# MosFetsDrive_2.net
KiCad netlist of a schematic drawn in Altium Designer
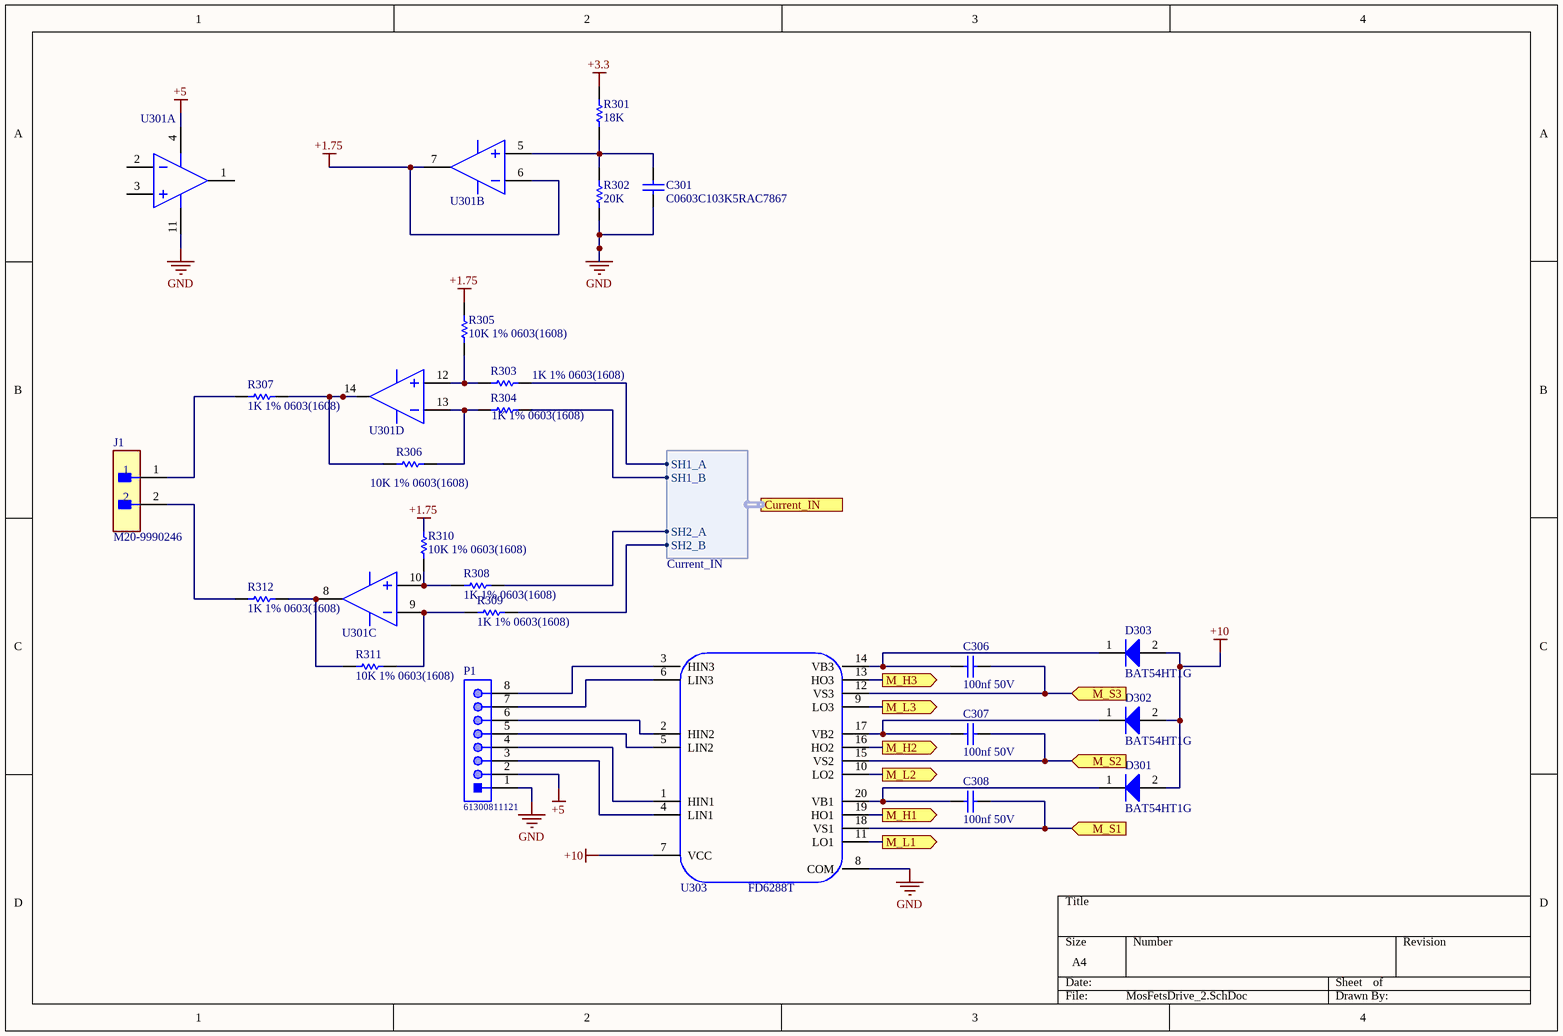
[diagram p0: MosFetsDrive_2.SchDoc]

(export (version "E")
  (design (tool "Eeschema 10.0.6"))
  (components
    (comp (ref "C301")
      (value "C0603C103K5RAC7867")
      (footprint "CAPC1608X87X35ML15T15")
      (fields (field (name "MANUFACTURER") "Kemet"))
      (libsource (lib "Altium Content Vault") (part "CAP"))
    )
    (comp (ref "C306")
      (value "100nf 50V")
      (footprint "CAPC1608X90X35LL15T15")
      (fields
        (field (name "MANUFACTURER") "AVX Interconnect / Elco")
        (field (name "PART NUMBER") "06035C102KAT2A")
      )
      (libsource (lib "Altium Content Vault") (part "CAP"))
    )
    (comp (ref "C307")
      (value "100nf 50V")
      (footprint "CAPC1608X90X35LL15T15")
      (fields
        (field (name "MANUFACTURER") "AVX Interconnect / Elco")
        (field (name "PART NUMBER") "06035C102KAT2A")
      )
      (libsource (lib "Altium Content Vault") (part "CAP"))
    )
    (comp (ref "C308")
      (value "100nf 50V")
      (footprint "CAPC1608X90X35LL15T15")
      (fields
        (field (name "MANUFACTURER") "AVX Interconnect / Elco")
        (field (name "PART NUMBER") "06035C102KAT2A")
      )
      (libsource (lib "Altium Content Vault") (part "CAP"))
    )
    (comp (ref "D301")
      (value "BAT54HT1G")
      (footprint "ONSC-SOD-323-2-477-02_V")
      (description "Schottky Barrier Diode, 2-Pin SOD-323, Pb-Free, Tape and Reel")
      (fields (field (name "MANUFACTURER") "On Semiconductor"))
      (libsource (lib "Altium Content Vault") (part "ONSC-D-K1A2-2"))
    )
    (comp (ref "D302")
      (value "BAT54HT1G")
      (footprint "ONSC-SOD-323-2-477-02_V")
      (description "Schottky Barrier Diode, 2-Pin SOD-323, Pb-Free, Tape and Reel")
      (fields (field (name "MANUFACTURER") "On Semiconductor"))
      (libsource (lib "Altium Content Vault") (part "ONSC-D-K1A2-2"))
    )
    (comp (ref "D303")
      (value "BAT54HT1G")
      (footprint "ONSC-SOD-323-2-477-02_V")
      (description "Schottky Barrier Diode, 2-Pin SOD-323, Pb-Free, Tape and Reel")
      (fields (field (name "MANUFACTURER") "On Semiconductor"))
      (libsource (lib "Altium Content Vault") (part "ONSC-D-K1A2-2"))
    )
    (comp (ref "J1")
      (value "M20-9990246")
      (footprint "FP-M20-9990246-MFG")
      (description "CONN HEADER VERT 2POS 2.54MM")
      (fields
        (field (name "OCTOPART") "https://octopart.com/m20-9990246-harwin-2590635")
        (field (name "MANUFACTURER") "Harwin")
      )
      (libsource (lib "Altium Content Vault") (part "3bc925449376181038e59eaffc5286c"))
    )
    (comp (ref "P1")
      (value "61300811121")
      (footprint "61300811121")
      (description "THT Vertical Pin Header WR-PHD, Pitch 2.54 mm, Single Row, 8 pins")
      (fields (field (name "MANUFACTURER") "Wurth Elektronik") (field (name "PUBLISHER") "WurthElektronik"))
      (libsource (lib "Altium Content Vault") (part "WE-CN-1P-M-R8"))
    )
    (comp (ref "R301")
      (value "18K")
      (footprint "RESC1608X55X30LL20T20")
      (fields (field (name "MANUFACTURER") "Panasonic") (field (name "PART NUMBER") "ERA3AEB102V"))
      (libsource (lib "Altium Content Vault") (part "RES"))
    )
    (comp (ref "R302")
      (value "20K")
      (footprint "RESC1608X55X30LL20T20")
      (fields (field (name "MANUFACTURER") "Panasonic") (field (name "PART NUMBER") "ERA3AEB102V"))
      (libsource (lib "Altium Content Vault") (part "RES"))
    )
    (comp (ref "R303")
      (value "1K 1% 0603(1608)")
      (footprint "RESC0603(1608)_N")
      (description "10K 0.1W 1% 0603 (1608 Metric)  SMD")
      (fields (field (name "POWER") "0.1 W") (field (name "TOLERANCE") "1 %"))
      (libsource (lib "Altium Content Vault") (part "RES"))
    )
    (comp (ref "R304")
      (value "1K 1% 0603(1608)")
      (footprint "RESC0603(1608)_N")
      (description "10K 0.1W 1% 0603 (1608 Metric)  SMD")
      (fields (field (name "POWER") "0.1 W") (field (name "TOLERANCE") "1 %"))
      (libsource (lib "Altium Content Vault") (part "RES"))
    )
    (comp (ref "R305")
      (value "10K 1% 0603(1608)")
      (footprint "RESC0603(1608)_N")
      (description "10K 0.1W 1% 0603 (1608 Metric)  SMD")
      (fields (field (name "POWER") "0.1 W") (field (name "TOLERANCE") "1 %"))
      (libsource (lib "Altium Content Vault") (part "RES"))
    )
    (comp (ref "R306")
      (value "10K 1% 0603(1608)")
      (footprint "RESC0603(1608)_N")
      (description "10K 0.1W 1% 0603 (1608 Metric)  SMD")
      (fields (field (name "POWER") "0.1 W") (field (name "TOLERANCE") "1 %"))
      (libsource (lib "Altium Content Vault") (part "RES"))
    )
    (comp (ref "R307")
      (value "1K 1% 0603(1608)")
      (footprint "RESC0603(1608)_N")
      (description "10K 0.1W 1% 0603 (1608 Metric)  SMD")
      (fields (field (name "POWER") "0.1 W") (field (name "TOLERANCE") "1 %"))
      (libsource (lib "Altium Content Vault") (part "RES"))
    )
    (comp (ref "R308")
      (value "1K 1% 0603(1608)")
      (footprint "RESC0603(1608)_N")
      (description "10K 0.1W 1% 0603 (1608 Metric)  SMD")
      (fields (field (name "POWER") "0.1 W") (field (name "TOLERANCE") "1 %"))
      (libsource (lib "Altium Content Vault") (part "RES"))
    )
    (comp (ref "R309")
      (value "1K 1% 0603(1608)")
      (footprint "RESC0603(1608)_N")
      (description "10K 0.1W 1% 0603 (1608 Metric)  SMD")
      (fields (field (name "POWER") "0.1 W") (field (name "TOLERANCE") "1 %"))
      (libsource (lib "Altium Content Vault") (part "RES"))
    )
    (comp (ref "R310")
      (value "10K 1% 0603(1608)")
      (footprint "RESC0603(1608)_N")
      (description "10K 0.1W 1% 0603 (1608 Metric)  SMD")
      (fields (field (name "POWER") "0.1 W") (field (name "TOLERANCE") "1 %"))
      (libsource (lib "Altium Content Vault") (part "RES"))
    )
    (comp (ref "R311")
      (value "10K 1% 0603(1608)")
      (footprint "RESC0603(1608)_N")
      (description "10K 0.1W 1% 0603 (1608 Metric)  SMD")
      (fields (field (name "POWER") "0.1 W") (field (name "TOLERANCE") "1 %"))
      (libsource (lib "Altium Content Vault") (part "RES"))
    )
    (comp (ref "R312")
      (value "1K 1% 0603(1608)")
      (footprint "RESC0603(1608)_N")
      (description "10K 0.1W 1% 0603 (1608 Metric)  SMD")
      (fields (field (name "POWER") "0.1 W") (field (name "TOLERANCE") "1 %"))
      (libsource (lib "Altium Content Vault") (part "RES"))
    )
    (comp (ref "U301")
      (value "~")
      (footprint "SOP-14_L8.6-W3.9-P1.27-LS6.0-BL")
      (fields (field (name "MANUFACTURER") "IDCHIP(英锐芯)") (field (name "MANUFACTURER PART") "LMV324"))
      (libsource (lib "altium-import") (part "root_2_LMV324_"))
    )
    (comp (ref "U303")
      (value "FD6288T")
      (footprint "TSSOP-20_L6.5-W4.4-P0.65-LS6.4-BL")
      (fields (field (name "MANUFACTURER") "Fortior Tech(峰岹)"))
      (libsource (lib "DF6288") (part "FD6288T"))
    )
  )
  (nets
    (net (code "2") (name "+1.75") (class "Default")
      (node (ref "R305") (pin "2") (pinfunction "2_2") (pintype "passive"))
      (node (ref "R310") (pin "2") (pinfunction "2_2") (pintype "passive"))
      (node (ref "U301") (pin "6") (pinfunction "2IN-_6") (pintype "passive"))
      (node (ref "U301") (pin "7") (pinfunction "2OUT_7") (pintype "passive"))
    )
    (net (code "3") (name "+3.3") (class "Default")
      (node (ref "R301") (pin "2") (pinfunction "2_2") (pintype "passive"))
    )
    (net (code "4") (name "+5") (class "Default")
      (node (ref "P1") (pin "2") (pinfunction "2_2") (pintype "passive"))
      (node (ref "U301") (pin "4") (pinfunction "VCC_4") (pintype "passive"))
    )
    (net (code "5") (name "+10") (class "Default")
      (node (ref "D301") (pin "2") (pinfunction "A_2") (pintype "passive"))
      (node (ref "D302") (pin "2") (pinfunction "A_2") (pintype "passive"))
      (node (ref "D303") (pin "2") (pinfunction "A_2") (pintype "passive"))
      (node (ref "U303") (pin "7") (pinfunction "VCC_7") (pintype "passive"))
    )
    (net (code "6") (name "/M_H1") (class "Default")
      (node (ref "U303") (pin "19") (pinfunction "HO1_19") (pintype "passive"))
    )
    (net (code "7") (name "/M_H2") (class "Default")
      (node (ref "U303") (pin "16") (pinfunction "HO2_16") (pintype "passive"))
    )
    (net (code "8") (name "/M_H3") (class "Default")
      (node (ref "U303") (pin "13") (pinfunction "HO3_13") (pintype "passive"))
    )
    (net (code "9") (name "/M_L1") (class "Default")
      (node (ref "U303") (pin "11") (pinfunction "LO1_11") (pintype "passive"))
    )
    (net (code "10") (name "/M_L2") (class "Default")
      (node (ref "U303") (pin "10") (pinfunction "LO2_10") (pintype "passive"))
    )
    (net (code "11") (name "/M_L3") (class "Default")
      (node (ref "U303") (pin "9") (pinfunction "LO3_9") (pintype "passive"))
    )
    (net (code "12") (name "/M_S1") (class "Default")
      (node (ref "C308") (pin "2") (pinfunction "2_2") (pintype "passive"))
      (node (ref "U303") (pin "18") (pinfunction "VS1_18") (pintype "passive"))
    )
    (net (code "13") (name "/M_S2") (class "Default")
      (node (ref "C307") (pin "2") (pinfunction "2_2") (pintype "passive"))
      (node (ref "U303") (pin "15") (pinfunction "VS2_15") (pintype "passive"))
    )
    (net (code "14") (name "/M_S3") (class "Default")
      (node (ref "C306") (pin "2") (pinfunction "2_2") (pintype "passive"))
      (node (ref "U303") (pin "12") (pinfunction "VS3_12") (pintype "passive"))
    )
    (net (code "15") (name "/SH1_A") (class "Default")
      (node (ref "R303") (pin "2") (pinfunction "2_2") (pintype "passive"))
    )
    (net (code "16") (name "/SH1_B") (class "Default")
      (node (ref "R304") (pin "2") (pinfunction "2_2") (pintype "passive"))
    )
    (net (code "17") (name "/SH2_A") (class "Default")
      (node (ref "R308") (pin "2") (pinfunction "2_2") (pintype "passive"))
    )
    (net (code "18") (name "/SH2_B") (class "Default")
      (node (ref "R309") (pin "2") (pinfunction "2_2") (pintype "passive"))
    )
    (net (code "20") (name "GND") (class "Default")
      (node (ref "C301") (pin "1") (pinfunction "1_1") (pintype "passive"))
      (node (ref "P1") (pin "1") (pinfunction "1_1") (pintype "passive"))
      (node (ref "R302") (pin "1") (pinfunction "1_1") (pintype "passive"))
      (node (ref "U301") (pin "11") (pinfunction "GND_11") (pintype "passive"))
      (node (ref "U303") (pin "8") (pinfunction "COM_8") (pintype "passive"))
    )
    (net (code "21") (name "Net-(D301-K)") (class "Default")
      (node (ref "C308") (pin "1") (pinfunction "1_1") (pintype "passive"))
      (node (ref "D301") (pin "1") (pinfunction "K_1") (pintype "passive"))
      (node (ref "U303") (pin "20") (pinfunction "VB1_20") (pintype "passive"))
    )
    (net (code "22") (name "Net-(D302-K)") (class "Default")
      (node (ref "C307") (pin "1") (pinfunction "1_1") (pintype "passive"))
      (node (ref "D302") (pin "1") (pinfunction "K_1") (pintype "passive"))
      (node (ref "U303") (pin "17") (pinfunction "VB2_17") (pintype "passive"))
    )
    (net (code "23") (name "Net-(D303-K)") (class "Default")
      (node (ref "C306") (pin "1") (pinfunction "1_1") (pintype "passive"))
      (node (ref "D303") (pin "1") (pinfunction "K_1") (pintype "passive"))
      (node (ref "U303") (pin "14") (pinfunction "VB3_14") (pintype "passive"))
    )
    (net (code "24") (name "Net-(J1-Pad1)") (class "Default")
      (node (ref "J1") (pin "1") (pinfunction "1_1") (pintype "passive"))
      (node (ref "R307") (pin "1") (pinfunction "1_1") (pintype "passive"))
    )
    (net (code "25") (name "Net-(J1-Pad2)") (class "Default")
      (node (ref "J1") (pin "2") (pinfunction "2_2") (pintype "passive"))
      (node (ref "R312") (pin "1") (pinfunction "1_1") (pintype "passive"))
    )
    (net (code "26") (name "Net-(U301B-2IN+)") (class "Default")
      (node (ref "C301") (pin "2") (pinfunction "2_2") (pintype "passive"))
      (node (ref "R301") (pin "1") (pinfunction "1_1") (pintype "passive"))
      (node (ref "R302") (pin "2") (pinfunction "2_2") (pintype "passive"))
      (node (ref "U301") (pin "5") (pinfunction "2IN+_5") (pintype "passive"))
    )
    (net (code "27") (name "Net-(U301C-3IN+)") (class "Default")
      (node (ref "R308") (pin "1") (pinfunction "1_1") (pintype "passive"))
      (node (ref "R310") (pin "1") (pinfunction "1_1") (pintype "passive"))
      (node (ref "U301") (pin "10") (pinfunction "3IN+_10") (pintype "passive"))
    )
    (net (code "28") (name "Net-(U301C-3IN-)") (class "Default")
      (node (ref "R309") (pin "1") (pinfunction "1_1") (pintype "passive"))
      (node (ref "R311") (pin "2") (pinfunction "2_2") (pintype "passive"))
      (node (ref "U301") (pin "9") (pinfunction "3IN-_9") (pintype "passive"))
    )
    (net (code "29") (name "Net-(U301C-3OUT)") (class "Default")
      (node (ref "R311") (pin "1") (pinfunction "1_1") (pintype "passive"))
      (node (ref "R312") (pin "2") (pinfunction "2_2") (pintype "passive"))
      (node (ref "U301") (pin "8") (pinfunction "3OUT_8") (pintype "passive"))
    )
    (net (code "30") (name "Net-(U301D-4IN+)") (class "Default")
      (node (ref "R303") (pin "1") (pinfunction "1_1") (pintype "passive"))
      (node (ref "R305") (pin "1") (pinfunction "1_1") (pintype "passive"))
      (node (ref "U301") (pin "12") (pinfunction "4IN+_12") (pintype "passive"))
    )
    (net (code "31") (name "Net-(U301D-4IN-)") (class "Default")
      (node (ref "R304") (pin "1") (pinfunction "1_1") (pintype "passive"))
      (node (ref "R306") (pin "2") (pinfunction "2_2") (pintype "passive"))
      (node (ref "U301") (pin "13") (pinfunction "4IN-_13") (pintype "passive"))
    )
    (net (code "32") (name "Net-(U301D-4OUT)") (class "Default")
      (node (ref "R306") (pin "1") (pinfunction "1_1") (pintype "passive"))
      (node (ref "R307") (pin "2") (pinfunction "2_2") (pintype "passive"))
      (node (ref "U301") (pin "14") (pinfunction "4OUT_14") (pintype "passive"))
    )
    (net (code "33") (name "Net-(U303-HIN1)") (class "Default")
      (node (ref "P1") (pin "4") (pinfunction "4_4") (pintype "passive"))
      (node (ref "U303") (pin "1") (pinfunction "HIN1_1") (pintype "passive"))
    )
    (net (code "34") (name "Net-(U303-HIN2)") (class "Default")
      (node (ref "P1") (pin "6") (pinfunction "6_6") (pintype "passive"))
      (node (ref "U303") (pin "2") (pinfunction "HIN2_2") (pintype "passive"))
    )
    (net (code "35") (name "Net-(U303-HIN3)") (class "Default")
      (node (ref "P1") (pin "8") (pinfunction "8_8") (pintype "passive"))
      (node (ref "U303") (pin "3") (pinfunction "HIN3_3") (pintype "passive"))
    )
    (net (code "36") (name "Net-(U303-LIN1)") (class "Default")
      (node (ref "P1") (pin "3") (pinfunction "3_3") (pintype "passive"))
      (node (ref "U303") (pin "4") (pinfunction "LIN1_4") (pintype "passive"))
    )
    (net (code "37") (name "Net-(U303-LIN2)") (class "Default")
      (node (ref "P1") (pin "5") (pinfunction "5_5") (pintype "passive"))
      (node (ref "U303") (pin "5") (pinfunction "LIN2_5") (pintype "passive"))
    )
    (net (code "38") (name "Net-(U303-LIN3)") (class "Default")
      (node (ref "P1") (pin "7") (pinfunction "7_7") (pintype "passive"))
      (node (ref "U303") (pin "6") (pinfunction "LIN3_6") (pintype "passive"))
    )
    (net (code "39") (name "unconnected-(U301A-1IN+-Pad3)") (class "Default")
      (node (ref "U301") (pin "3") (pinfunction "1IN+_3") (pintype "passive"))
    )
    (net (code "40") (name "unconnected-(U301A-1IN--Pad2)") (class "Default")
      (node (ref "U301") (pin "2") (pinfunction "1IN-_2") (pintype "passive"))
    )
    (net (code "41") (name "unconnected-(U301A-1OUT-Pad1)") (class "Default")
      (node (ref "U301") (pin "1") (pinfunction "1OUT_1") (pintype "passive"))
    )
  )
)
